# BOX.net
KiCad netlist of a schematic drawn in Altium Designer
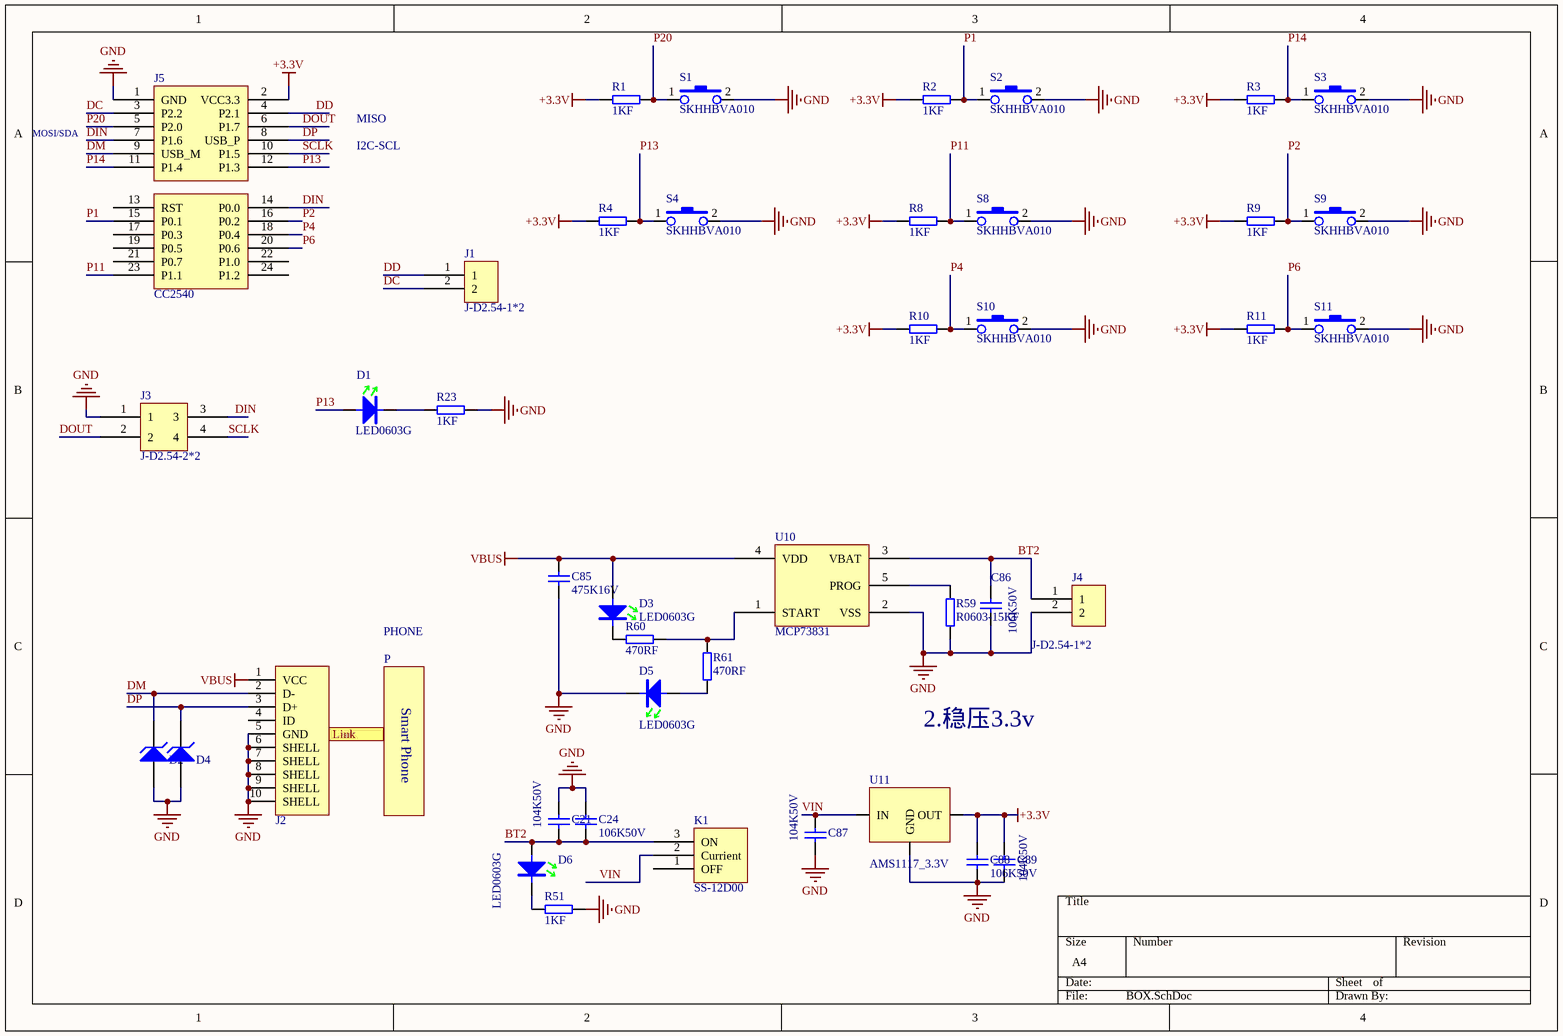
[diagram p0: BOX.SchDoc]

(export (version "E")
  (design (tool "Eeschema 10.0.6"))
  (components
    (comp (ref "C21")
      (value "104K50V")
      (footprint "C0603")
      (description "贴片电容-陶瓷")
      (libsource (lib "Capacitor") (part "C0603X7R-104K50V"))
    )
    (comp (ref "C24")
      (value "106K50V")
      (footprint "C0603")
      (description "贴片电容-陶瓷")
      (libsource (lib "Capacitor") (part "C0603X7R-106K50V"))
    )
    (comp (ref "C85")
      (value "475K16V")
      (footprint "C0603")
      (description "贴片电容-陶瓷")
      (libsource (lib "Capacitor") (part "C0603X7R-475K16V"))
    )
    (comp (ref "C86")
      (value "106K50V")
      (footprint "C0603")
      (description "贴片电容-陶瓷")
      (libsource (lib "Capacitor") (part "C0603X7R-106K50V"))
    )
    (comp (ref "C87")
      (value "104K50V")
      (footprint "C0603")
      (description "贴片电容-陶瓷")
      (libsource (lib "Capacitor") (part "C0603X7R-104K50V"))
    )
    (comp (ref "C88")
      (value "106K50V")
      (footprint "C0603")
      (description "贴片电容-陶瓷")
      (libsource (lib "Capacitor") (part "C0603X7R-106K50V"))
    )
    (comp (ref "C89")
      (value "104K50V")
      (footprint "C0603")
      (description "贴片电容-陶瓷")
      (libsource (lib "Capacitor") (part "C0603X7R-104K50V"))
    )
    (comp (ref "D1")
      (value "LED0603G")
      (footprint "D-LED0603G")
      (description "贴片二极管-LED")
      (libsource (lib "aiwacV2.0") (part "DLED-0603-G"))
    )
    (comp (ref "D2")
      (value "ESDA_TR1/0603")
      (footprint "HS_0603D")
      (description "Zener Diode")
      (fields (field (name "PUBLISHER") "*"))
      (libsource (lib "aiwacV2.0") (part "D Zener"))
    )
    (comp (ref "D3")
      (value "LED0603G")
      (footprint "D-LED0603G")
      (description "贴片二极管-LED")
      (libsource (lib "Diode") (part "DLED-0603-G"))
    )
    (comp (ref "D4")
      (value "ESDA_TR1/0603")
      (footprint "HS_0603D")
      (description "Zener Diode")
      (fields (field (name "PUBLISHER") "*"))
      (libsource (lib "aiwacV2.0") (part "D Zener"))
    )
    (comp (ref "D5")
      (value "LED0603G")
      (footprint "D-LED0603G")
      (description "贴片二极管-LED")
      (libsource (lib "Diode") (part "DLED-0603-G"))
    )
    (comp (ref "D6")
      (value "LED0603G")
      (footprint "D-LED0603G")
      (description "贴片二极管-LED")
      (libsource (lib "aiwacV2.0") (part "DLED-0603-G"))
    )
    (comp (ref "J1")
      (value "J-D2.54-1*2")
      (footprint "D2.54-1*2P")
      (libsource (lib "Connector") (part "J-D2.54-1*2单排"))
    )
    (comp (ref "J2")
      (value "USB-MINI-SOCKET")
      (footprint "MICRO-USB - 5.9")
      (description "USB-A卧式插座")
      (libsource (lib "epic2") (part "J-USB-MINI-SOCKET"))
    )
    (comp (ref "J3")
      (value "J-D2.54-2*2")
      (footprint "D2.54-2*2P")
      (description "双排排针-直针")
      (libsource (lib "diapers_1") (part "J-D2.54-2*2双排"))
    )
    (comp (ref "J4")
      (value "J-D2.54-1*2")
      (footprint "D2.54-1*2P")
      (libsource (lib "Connector") (part "J-D2.54-1*2单排"))
    )
    (comp (ref "J5")
      (value "CC2540")
      (footprint "CC2540")
      (description "蓝牙主控模块的接口")
      (libsource (lib "diapers_1") (part "CC2540"))
    )
    (comp (ref "K1")
      (value "SS-12D00")
      (footprint "SS-12D00")
      (libsource (lib "Key") (part "SS-12D00(1P2T) 立式 柄高5MM"))
    )
    (comp (ref "P") (value "PHONE") (libsource (lib "epic") (part "PHONE")))
    (comp (ref "R1")
      (value "1KF")
      (footprint "R0603")
      (description "贴片电阻-通用")
      (libsource (lib "diapers_1") (part "R0603-1KF"))
    )
    (comp (ref "R2")
      (value "1KF")
      (footprint "R0603")
      (description "贴片电阻-通用")
      (libsource (lib "diapers_1") (part "R0603-1KF"))
    )
    (comp (ref "R3")
      (value "1KF")
      (footprint "R0603")
      (description "贴片电阻-通用")
      (libsource (lib "diapers_1") (part "R0603-1KF"))
    )
    (comp (ref "R4")
      (value "1KF")
      (footprint "R0603")
      (description "贴片电阻-通用")
      (libsource (lib "diapers_1") (part "R0603-1KF"))
    )
    (comp (ref "R8")
      (value "1KF")
      (footprint "R0603")
      (description "贴片电阻-通用")
      (libsource (lib "diapers_1") (part "R0603-1KF"))
    )
    (comp (ref "R9")
      (value "1KF")
      (footprint "R0603")
      (description "贴片电阻-通用")
      (libsource (lib "diapers_1") (part "R0603-1KF"))
    )
    (comp (ref "R10")
      (value "1KF")
      (footprint "R0603")
      (description "贴片电阻-通用")
      (libsource (lib "diapers_1") (part "R0603-1KF"))
    )
    (comp (ref "R11")
      (value "1KF")
      (footprint "R0603")
      (description "贴片电阻-通用")
      (libsource (lib "diapers_1") (part "R0603-1KF"))
    )
    (comp (ref "R23")
      (value "1KF")
      (footprint "R0603")
      (description "贴片电阻-通用")
      (libsource (lib "diapers_1") (part "R0603-1KF"))
    )
    (comp (ref "R51")
      (value "1KF")
      (footprint "R0603")
      (description "贴片电阻-通用")
      (libsource (lib "Resistor") (part "R0603-1KF"))
    )
    (comp (ref "R59")
      (value "R0603-15KF")
      (footprint "R0603")
      (description "贴片电容-通用")
      (libsource (lib "Resistor") (part "R0603-15KF"))
    )
    (comp (ref "R60")
      (value "470RF")
      (footprint "R0603")
      (description "贴片电阻-通用")
      (libsource (lib "Resistor") (part "R0603-470RF"))
    )
    (comp (ref "R61")
      (value "470RF")
      (footprint "R0603")
      (description "贴片电阻-通用")
      (libsource (lib "Resistor") (part "R0603-470RF"))
    )
    (comp (ref "S1")
      (value "SKHHBVA010")
      (footprint "S-SKHHBVA010")
      (description "轻触按键")
      (libsource (lib "Key") (part "S-SKHHBVA010"))
    )
    (comp (ref "S2")
      (value "SKHHBVA010")
      (footprint "S-SKHHBVA010")
      (description "轻触按键")
      (libsource (lib "Key") (part "S-SKHHBVA010"))
    )
    (comp (ref "S3")
      (value "SKHHBVA010")
      (footprint "S-SKHHBVA010")
      (description "轻触按键")
      (libsource (lib "Key") (part "S-SKHHBVA010"))
    )
    (comp (ref "S4")
      (value "SKHHBVA010")
      (footprint "S-SKHHBVA010")
      (description "轻触按键")
      (libsource (lib "Key") (part "S-SKHHBVA010"))
    )
    (comp (ref "S8")
      (value "SKHHBVA010")
      (footprint "S-SKHHBVA010")
      (description "轻触按键")
      (libsource (lib "Key") (part "S-SKHHBVA010"))
    )
    (comp (ref "S9")
      (value "SKHHBVA010")
      (footprint "S-SKHHBVA010")
      (description "轻触按键")
      (libsource (lib "Key") (part "S-SKHHBVA010"))
    )
    (comp (ref "S10")
      (value "SKHHBVA010")
      (footprint "S-SKHHBVA010")
      (description "轻触按键")
      (libsource (lib "Key") (part "S-SKHHBVA010"))
    )
    (comp (ref "S11")
      (value "SKHHBVA010")
      (footprint "S-SKHHBVA010")
      (description "轻触按键")
      (libsource (lib "Key") (part "S-SKHHBVA010"))
    )
    (comp (ref "U10")
      (value "MCP73831")
      (footprint "SOT23-5N")
      (description "charge IC")
      (libsource (lib "IC") (part "MCP73831"))
    )
    (comp (ref "U11")
      (value "AMS1117_3.3V")
      (footprint "SOT-223")
      (libsource (lib "IC") (part "AMS1117-3.3V"))
    )
  )
  (nets
    (net (code "1") (name "+3.3V") (class "Default")
      (node (ref "C88") (pin "2") (pinfunction "2_2") (pintype "passive"))
      (node (ref "C89") (pin "1") (pinfunction "1_1") (pintype "passive"))
      (node (ref "J5") (pin "2") (pinfunction "VCC3.3_2") (pintype "passive"))
      (node (ref "R1") (pin "1") (pinfunction "1_1") (pintype "passive"))
      (node (ref "R10") (pin "1") (pinfunction "1_1") (pintype "passive"))
      (node (ref "R11") (pin "1") (pinfunction "1_1") (pintype "passive"))
      (node (ref "R2") (pin "1") (pinfunction "1_1") (pintype "passive"))
      (node (ref "R3") (pin "1") (pinfunction "1_1") (pintype "passive"))
      (node (ref "R4") (pin "1") (pinfunction "1_1") (pintype "passive"))
      (node (ref "R8") (pin "1") (pinfunction "1_1") (pintype "passive"))
      (node (ref "R9") (pin "1") (pinfunction "1_1") (pintype "passive"))
      (node (ref "U11") (pin "2") (pinfunction "OUT_2") (pintype "passive"))
    )
    (net (code "2") (name "/BT2") (class "Default")
      (node (ref "C21") (pin "2") (pinfunction "2_2") (pintype "passive"))
      (node (ref "C24") (pin "1") (pinfunction "1_1") (pintype "passive"))
      (node (ref "C86") (pin "1") (pinfunction "1_1") (pintype "passive"))
      (node (ref "D6") (pin "1") (pinfunction "1_1") (pintype "passive"))
      (node (ref "J4") (pin "1") (pinfunction "1_1") (pintype "passive"))
      (node (ref "K1") (pin "3") (pinfunction "ON_3") (pintype "passive"))
      (node (ref "U10") (pin "3") (pinfunction "VBAT_3") (pintype "passive"))
    )
    (net (code "3") (name "/DC") (class "Default")
      (node (ref "J1") (pin "2") (pinfunction "2_2") (pintype "passive"))
      (node (ref "J5") (pin "3") (pinfunction "P2.2_3") (pintype "passive"))
    )
    (net (code "4") (name "/DD") (class "Default")
      (node (ref "J1") (pin "1") (pinfunction "1_1") (pintype "passive"))
      (node (ref "J5") (pin "4") (pinfunction "P2.1_4") (pintype "passive"))
    )
    (net (code "5") (name "/DIN") (class "Default")
      (node (ref "J3") (pin "3") (pinfunction "3_3") (pintype "passive"))
      (node (ref "J5") (pin "14") (pinfunction "P0.0_14") (pintype "passive"))
      (node (ref "J5") (pin "7") (pinfunction "P1.6_7") (pintype "passive"))
    )
    (net (code "6") (name "/DM") (class "Default")
      (node (ref "D2") (pin "2") (pinfunction "K_2") (pintype "passive"))
      (node (ref "J2") (pin "2") (pinfunction "D-_2") (pintype "passive"))
      (node (ref "J5") (pin "9") (pinfunction "USB_M_9") (pintype "passive"))
    )
    (net (code "7") (name "/DOUT") (class "Default")
      (node (ref "J3") (pin "2") (pinfunction "2_2") (pintype "passive"))
      (node (ref "J5") (pin "6") (pinfunction "P1.7_6") (pintype "passive"))
    )
    (net (code "8") (name "/DP") (class "Default")
      (node (ref "D4") (pin "2") (pinfunction "K_2") (pintype "passive"))
      (node (ref "J2") (pin "3") (pinfunction "D+_3") (pintype "passive"))
      (node (ref "J5") (pin "8") (pinfunction "USB_P_8") (pintype "passive"))
    )
    (net (code "10") (name "/P1") (class "Default")
      (node (ref "J5") (pin "15") (pinfunction "P0.1_15") (pintype "passive"))
      (node (ref "R2") (pin "2") (pinfunction "2_2") (pintype "passive"))
      (node (ref "S2") (pin "1") (pinfunction "1_1") (pintype "passive"))
    )
    (net (code "11") (name "/P2") (class "Default")
      (node (ref "J5") (pin "16") (pinfunction "P0.2_16") (pintype "passive"))
      (node (ref "R9") (pin "2") (pinfunction "2_2") (pintype "passive"))
      (node (ref "S9") (pin "1") (pinfunction "1_1") (pintype "passive"))
    )
    (net (code "12") (name "/P4") (class "Default")
      (node (ref "J5") (pin "18") (pinfunction "P0.4_18") (pintype "passive"))
      (node (ref "R10") (pin "2") (pinfunction "2_2") (pintype "passive"))
      (node (ref "S10") (pin "1") (pinfunction "1_1") (pintype "passive"))
    )
    (net (code "13") (name "/P6") (class "Default")
      (node (ref "J5") (pin "20") (pinfunction "P0.6_20") (pintype "passive"))
      (node (ref "R11") (pin "2") (pinfunction "2_2") (pintype "passive"))
      (node (ref "S11") (pin "1") (pinfunction "1_1") (pintype "passive"))
    )
    (net (code "14") (name "/P11") (class "Default")
      (node (ref "J5") (pin "23") (pinfunction "P1.1_23") (pintype "passive"))
      (node (ref "R8") (pin "2") (pinfunction "2_2") (pintype "passive"))
      (node (ref "S8") (pin "1") (pinfunction "1_1") (pintype "passive"))
    )
    (net (code "15") (name "/P13") (class "Default")
      (node (ref "D1") (pin "1") (pinfunction "1_1") (pintype "passive"))
      (node (ref "J5") (pin "12") (pinfunction "P1.3_12") (pintype "passive"))
      (node (ref "R4") (pin "2") (pinfunction "2_2") (pintype "passive"))
      (node (ref "S4") (pin "1") (pinfunction "1_1") (pintype "passive"))
    )
    (net (code "16") (name "/P14") (class "Default")
      (node (ref "J5") (pin "11") (pinfunction "P1.4_11") (pintype "passive"))
      (node (ref "R3") (pin "2") (pinfunction "2_2") (pintype "passive"))
      (node (ref "S3") (pin "1") (pinfunction "1_1") (pintype "passive"))
    )
    (net (code "17") (name "/P20") (class "Default")
      (node (ref "J5") (pin "5") (pinfunction "P2.0_5") (pintype "passive"))
      (node (ref "R1") (pin "2") (pinfunction "2_2") (pintype "passive"))
      (node (ref "S1") (pin "1") (pinfunction "1_1") (pintype "passive"))
    )
    (net (code "18") (name "/SCLK") (class "Default")
      (node (ref "J3") (pin "4") (pinfunction "4_4") (pintype "passive"))
      (node (ref "J5") (pin "10") (pinfunction "P1.5_10") (pintype "passive"))
    )
    (net (code "19") (name "/VIN") (class "Default")
      (node (ref "C87") (pin "1") (pinfunction "1_1") (pintype "passive"))
      (node (ref "K1") (pin "2") (pinfunction "Currient_2") (pintype "passive"))
      (node (ref "U11") (pin "3") (pinfunction "IN_3") (pintype "passive"))
    )
    (net (code "20") (name "GND") (class "Default")
      (node (ref "C21") (pin "1") (pinfunction "1_1") (pintype "passive"))
      (node (ref "C24") (pin "2") (pinfunction "2_2") (pintype "passive"))
      (node (ref "C85") (pin "2") (pinfunction "2_2") (pintype "passive"))
      (node (ref "C86") (pin "2") (pinfunction "2_2") (pintype "passive"))
      (node (ref "C87") (pin "2") (pinfunction "2_2") (pintype "passive"))
      (node (ref "C88") (pin "1") (pinfunction "1_1") (pintype "passive"))
      (node (ref "C89") (pin "2") (pinfunction "2_2") (pintype "passive"))
      (node (ref "D2") (pin "1") (pinfunction "A_1") (pintype "passive"))
      (node (ref "D4") (pin "1") (pinfunction "A_1") (pintype "passive"))
      (node (ref "D5") (pin "2") (pinfunction "2_2") (pintype "passive"))
      (node (ref "J2") (pin "10") (pinfunction "SHELL_10") (pintype "passive"))
      (node (ref "J2") (pin "5") (pinfunction "GND_5") (pintype "passive"))
      (node (ref "J2") (pin "6") (pinfunction "SHELL_6") (pintype "passive"))
      (node (ref "J2") (pin "7") (pinfunction "SHELL_7") (pintype "passive"))
      (node (ref "J2") (pin "8") (pinfunction "SHELL_8") (pintype "passive"))
      (node (ref "J2") (pin "9") (pinfunction "SHELL_9") (pintype "passive"))
      (node (ref "J3") (pin "1") (pinfunction "1_1") (pintype "passive"))
      (node (ref "J4") (pin "2") (pinfunction "2_2") (pintype "passive"))
      (node (ref "J5") (pin "1") (pinfunction "GND_1") (pintype "passive"))
      (node (ref "R23") (pin "2") (pinfunction "2_2") (pintype "passive"))
      (node (ref "R51") (pin "2") (pinfunction "2_2") (pintype "passive"))
      (node (ref "R59") (pin "1") (pinfunction "1_1") (pintype "passive"))
      (node (ref "S1") (pin "2") (pinfunction "2_2") (pintype "passive"))
      (node (ref "S10") (pin "2") (pinfunction "2_2") (pintype "passive"))
      (node (ref "S11") (pin "2") (pinfunction "2_2") (pintype "passive"))
      (node (ref "S2") (pin "2") (pinfunction "2_2") (pintype "passive"))
      (node (ref "S3") (pin "2") (pinfunction "2_2") (pintype "passive"))
      (node (ref "S4") (pin "2") (pinfunction "2_2") (pintype "passive"))
      (node (ref "S8") (pin "2") (pinfunction "2_2") (pintype "passive"))
      (node (ref "S9") (pin "2") (pinfunction "2_2") (pintype "passive"))
      (node (ref "U10") (pin "2") (pinfunction "VSS_2") (pintype "passive"))
      (node (ref "U11") (pin "1") (pinfunction "GND_1") (pintype "passive"))
    )
    (net (code "21") (name "Net-(D1-Pad2)") (class "Default")
      (node (ref "D1") (pin "2") (pinfunction "2_2") (pintype "passive"))
      (node (ref "R23") (pin "1") (pinfunction "1_1") (pintype "passive"))
    )
    (net (code "22") (name "Net-(D3-Pad2)") (class "Default")
      (node (ref "D3") (pin "2") (pinfunction "2_2") (pintype "passive"))
      (node (ref "R60") (pin "1") (pinfunction "1_1") (pintype "passive"))
    )
    (net (code "23") (name "Net-(D5-Pad1)") (class "Default")
      (node (ref "D5") (pin "1") (pinfunction "1_1") (pintype "passive"))
      (node (ref "R61") (pin "1") (pinfunction "1_1") (pintype "passive"))
    )
    (net (code "24") (name "Net-(D6-Pad2)") (class "Default")
      (node (ref "D6") (pin "2") (pinfunction "2_2") (pintype "passive"))
      (node (ref "R51") (pin "1") (pinfunction "1_1") (pintype "passive"))
    )
    (net (code "25") (name "Net-(U10-PROG)") (class "Default")
      (node (ref "R59") (pin "2") (pinfunction "2_2") (pintype "passive"))
      (node (ref "U10") (pin "5") (pinfunction "PROG_5") (pintype "passive"))
    )
    (net (code "26") (name "Net-(U10-START)") (class "Default")
      (node (ref "R60") (pin "2") (pinfunction "2_2") (pintype "passive"))
      (node (ref "R61") (pin "2") (pinfunction "2_2") (pintype "passive"))
      (node (ref "U10") (pin "1") (pinfunction "START_1") (pintype "passive"))
    )
    (net (code "27") (name "VBUS") (class "Default")
      (node (ref "C85") (pin "1") (pinfunction "1_1") (pintype "passive"))
      (node (ref "D3") (pin "1") (pinfunction "1_1") (pintype "passive"))
      (node (ref "J2") (pin "1") (pinfunction "VCC_1") (pintype "passive"))
      (node (ref "U10") (pin "4") (pinfunction "VDD_4") (pintype "passive"))
    )
    (net (code "28") (name "unconnected-(J2-ID-Pad4)") (class "Default")
      (node (ref "J2") (pin "4") (pinfunction "ID_4") (pintype "passive"))
    )
    (net (code "29") (name "unconnected-(J5-P0.3-Pad17)") (class "Default")
      (node (ref "J5") (pin "17") (pinfunction "P0.3_17") (pintype "passive"))
    )
    (net (code "30") (name "unconnected-(J5-P0.5-Pad19)") (class "Default")
      (node (ref "J5") (pin "19") (pinfunction "P0.5_19") (pintype "passive"))
    )
    (net (code "31") (name "unconnected-(J5-P0.7-Pad21)") (class "Default")
      (node (ref "J5") (pin "21") (pinfunction "P0.7_21") (pintype "passive"))
    )
    (net (code "32") (name "unconnected-(J5-P1.0-Pad22)") (class "Default")
      (node (ref "J5") (pin "22") (pinfunction "P1.0_22") (pintype "passive"))
    )
    (net (code "33") (name "unconnected-(J5-P1.2-Pad24)") (class "Default")
      (node (ref "J5") (pin "24") (pinfunction "P1.2_24") (pintype "passive"))
    )
    (net (code "34") (name "unconnected-(J5-RST-Pad13)") (class "Default")
      (node (ref "J5") (pin "13") (pinfunction "RST_13") (pintype "passive"))
    )
    (net (code "35") (name "unconnected-(K1-OFF-Pad1)") (class "Default")
      (node (ref "K1") (pin "1") (pinfunction "OFF_1") (pintype "passive"))
    )
  )
)
